# barometer-throughhole.net
KiCad netlist of a schematic drawn in EAGLE
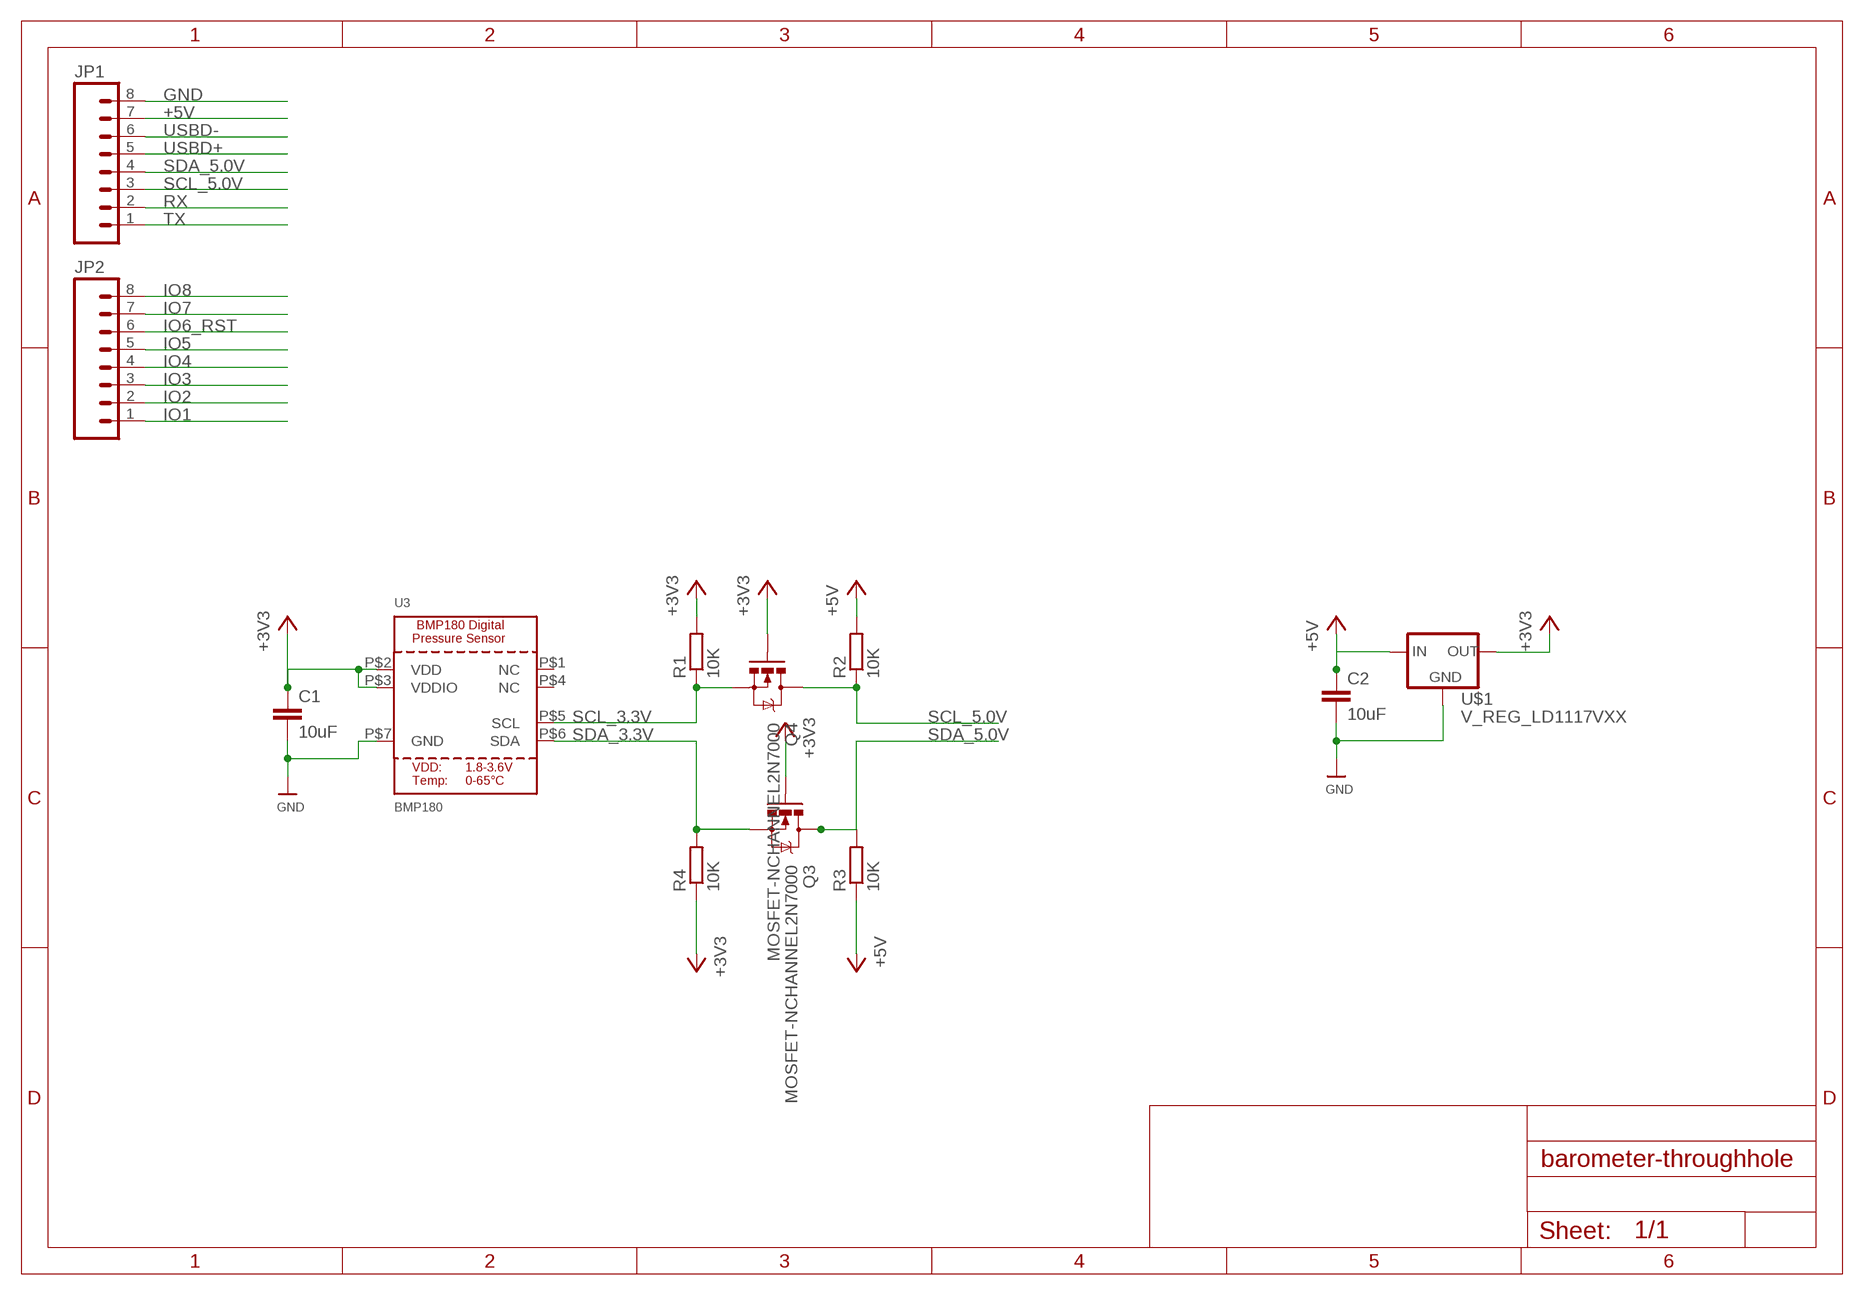
[diagram p0: schematic, sheet 1]

(export (version "E")
  (design (tool "Eeschema 10.0.6"))
  (components
    (comp (ref "C1")
      (value "10uF")
      (footprint "eagle-import:C025-030X050")
      (libsource (lib "eagle-import") (part "C-EU025-030X050"))
    )
    (comp (ref "C2")
      (value "10uF")
      (footprint "eagle-import:C025-030X050")
      (libsource (lib "eagle-import") (part "C-EU025-030X050"))
    )
    (comp (ref "JP1")
      (value "M081X08")
      (footprint "eagle-import:1X08")
      (libsource (lib "eagle-import") (part "M081X08"))
    )
    (comp (ref "JP2")
      (value "M081X08")
      (footprint "eagle-import:1X08")
      (libsource (lib "eagle-import") (part "M081X08"))
    )
    (comp (ref "Q3")
      (value "MOSFET-NCHANNEL2N7000")
      (footprint "eagle-import:TO-92")
      (libsource (lib "eagle-import") (part "MOSFET-NCHANNEL2N7000"))
    )
    (comp (ref "Q4")
      (value "MOSFET-NCHANNEL2N7000")
      (footprint "eagle-import:TO-92")
      (libsource (lib "eagle-import") (part "MOSFET-NCHANNEL2N7000"))
    )
    (comp (ref "R1")
      (value "10K")
      (footprint "eagle-import:0204_7")
      (libsource (lib "eagle-import") (part "R-EU_0204/7"))
    )
    (comp (ref "R2")
      (value "10K")
      (footprint "eagle-import:0204_7")
      (libsource (lib "eagle-import") (part "R-EU_0204/7"))
    )
    (comp (ref "R3")
      (value "10K")
      (footprint "eagle-import:0204_7")
      (libsource (lib "eagle-import") (part "R-EU_0204/7"))
    )
    (comp (ref "R4")
      (value "10K")
      (footprint "eagle-import:0204_7")
      (libsource (lib "eagle-import") (part "R-EU_0204/7"))
    )
    (comp (ref "U$1")
      (value "V_REG_LD1117VXX")
      (footprint "eagle-import:78XXL")
      (libsource (lib "eagle-import") (part "V_REG_LD1117VXX"))
    )
    (comp (ref "U3")
      (value "BMP180")
      (footprint "eagle-import:BMP180_EXTENDED")
      (libsource (lib "eagle-import") (part "BMP180EXT"))
    )
  )
  (nets
    (net (code "1") (name "+3V3") (class "Default")
      (node (ref "C1") (pin "1") (pinfunction "1_1") (pintype "passive"))
      (node (ref "Q3") (pin "2") (pinfunction "G_2") (pintype "passive"))
      (node (ref "Q4") (pin "2") (pinfunction "G_2") (pintype "passive"))
      (node (ref "R1") (pin "2") (pinfunction "2_2") (pintype "passive"))
      (node (ref "R4") (pin "1") (pinfunction "1_1") (pintype "passive"))
      (node (ref "U$1") (pin "GND") (pinfunction "OUT_GND") (pintype "output"))
      (node (ref "U3") (pin "P$2") (pinfunction "VDD_P$2") (pintype "power_in"))
      (node (ref "U3") (pin "P$3") (pinfunction "VDDIO_P$3") (pintype "power_in"))
    )
    (net (code "2") (name "+5V") (class "Default")
      (node (ref "C2") (pin "1") (pinfunction "1_1") (pintype "passive"))
      (node (ref "JP1") (pin "7") (pinfunction "7_7") (pintype "passive"))
      (node (ref "R2") (pin "2") (pinfunction "2_2") (pintype "passive"))
      (node (ref "R3") (pin "1") (pinfunction "1_1") (pintype "passive"))
      (node (ref "U$1") (pin "OUT") (pinfunction "IN_OUT") (pintype "input"))
    )
    (net (code "3") (name "/IO1") (class "Default")
      (node (ref "JP2") (pin "1") (pinfunction "1_1") (pintype "passive"))
    )
    (net (code "4") (name "/IO2") (class "Default")
      (node (ref "JP2") (pin "2") (pinfunction "2_2") (pintype "passive"))
    )
    (net (code "5") (name "/IO3") (class "Default")
      (node (ref "JP2") (pin "3") (pinfunction "3_3") (pintype "passive"))
    )
    (net (code "6") (name "/IO4") (class "Default")
      (node (ref "JP2") (pin "4") (pinfunction "4_4") (pintype "passive"))
    )
    (net (code "7") (name "/IO5") (class "Default")
      (node (ref "JP2") (pin "5") (pinfunction "5_5") (pintype "passive"))
    )
    (net (code "8") (name "/IO6_RST") (class "Default")
      (node (ref "JP2") (pin "6") (pinfunction "6_6") (pintype "passive"))
    )
    (net (code "9") (name "/IO7") (class "Default")
      (node (ref "JP2") (pin "7") (pinfunction "7_7") (pintype "passive"))
    )
    (net (code "10") (name "/IO8") (class "Default")
      (node (ref "JP2") (pin "8") (pinfunction "8_8") (pintype "passive"))
    )
    (net (code "11") (name "/RX") (class "Default")
      (node (ref "JP1") (pin "2") (pinfunction "2_2") (pintype "passive"))
    )
    (net (code "12") (name "/SCL_3.3V") (class "Default")
      (node (ref "Q4") (pin "1") (pinfunction "S_1") (pintype "passive"))
      (node (ref "R1") (pin "1") (pinfunction "1_1") (pintype "passive"))
      (node (ref "U3") (pin "P$5") (pinfunction "SCL_P$5") (pintype "bidirectional"))
    )
    (net (code "13") (name "/SCL_5.0V") (class "Default")
      (node (ref "JP1") (pin "3") (pinfunction "3_3") (pintype "passive"))
      (node (ref "Q4") (pin "3") (pinfunction "D_3") (pintype "passive"))
      (node (ref "R2") (pin "1") (pinfunction "1_1") (pintype "passive"))
    )
    (net (code "14") (name "/SDA_3.3V") (class "Default")
      (node (ref "Q3") (pin "1") (pinfunction "S_1") (pintype "passive"))
      (node (ref "R4") (pin "2") (pinfunction "2_2") (pintype "passive"))
      (node (ref "U3") (pin "P$6") (pinfunction "SDA_P$6") (pintype "bidirectional"))
    )
    (net (code "15") (name "/SDA_5.0V") (class "Default")
      (node (ref "JP1") (pin "4") (pinfunction "4_4") (pintype "passive"))
      (node (ref "Q3") (pin "3") (pinfunction "D_3") (pintype "passive"))
      (node (ref "R3") (pin "2") (pinfunction "2_2") (pintype "passive"))
    )
    (net (code "16") (name "/TX") (class "Default")
      (node (ref "JP1") (pin "1") (pinfunction "1_1") (pintype "passive"))
    )
    (net (code "17") (name "/USBD+") (class "Default")
      (node (ref "JP1") (pin "5") (pinfunction "5_5") (pintype "passive"))
    )
    (net (code "18") (name "/USBD-") (class "Default")
      (node (ref "JP1") (pin "6") (pinfunction "6_6") (pintype "passive"))
    )
    (net (code "19") (name "GND") (class "Default")
      (node (ref "C1") (pin "2") (pinfunction "2_2") (pintype "passive"))
      (node (ref "C2") (pin "2") (pinfunction "2_2") (pintype "passive"))
      (node (ref "JP1") (pin "8") (pinfunction "8_8") (pintype "passive"))
      (node (ref "U$1") (pin "IN") (pinfunction "GND_IN") (pintype "input"))
      (node (ref "U3") (pin "P$7") (pinfunction "GND_P$7") (pintype "power_in"))
    )
    (net (code "20") (name "unconnected-(U3-NC-PadP$1)") (class "Default")
      (node (ref "U3") (pin "P$1") (pinfunction "NC_P$1") (pintype "no_connect"))
    )
    (net (code "21") (name "unconnected-(U3-NC-PadP$4)") (class "Default")
      (node (ref "U3") (pin "P$4") (pinfunction "NC_P$4") (pintype "no_connect"))
    )
  )
)
